# USBandPOWER.net
KiCad netlist of a schematic drawn in Altium Designer
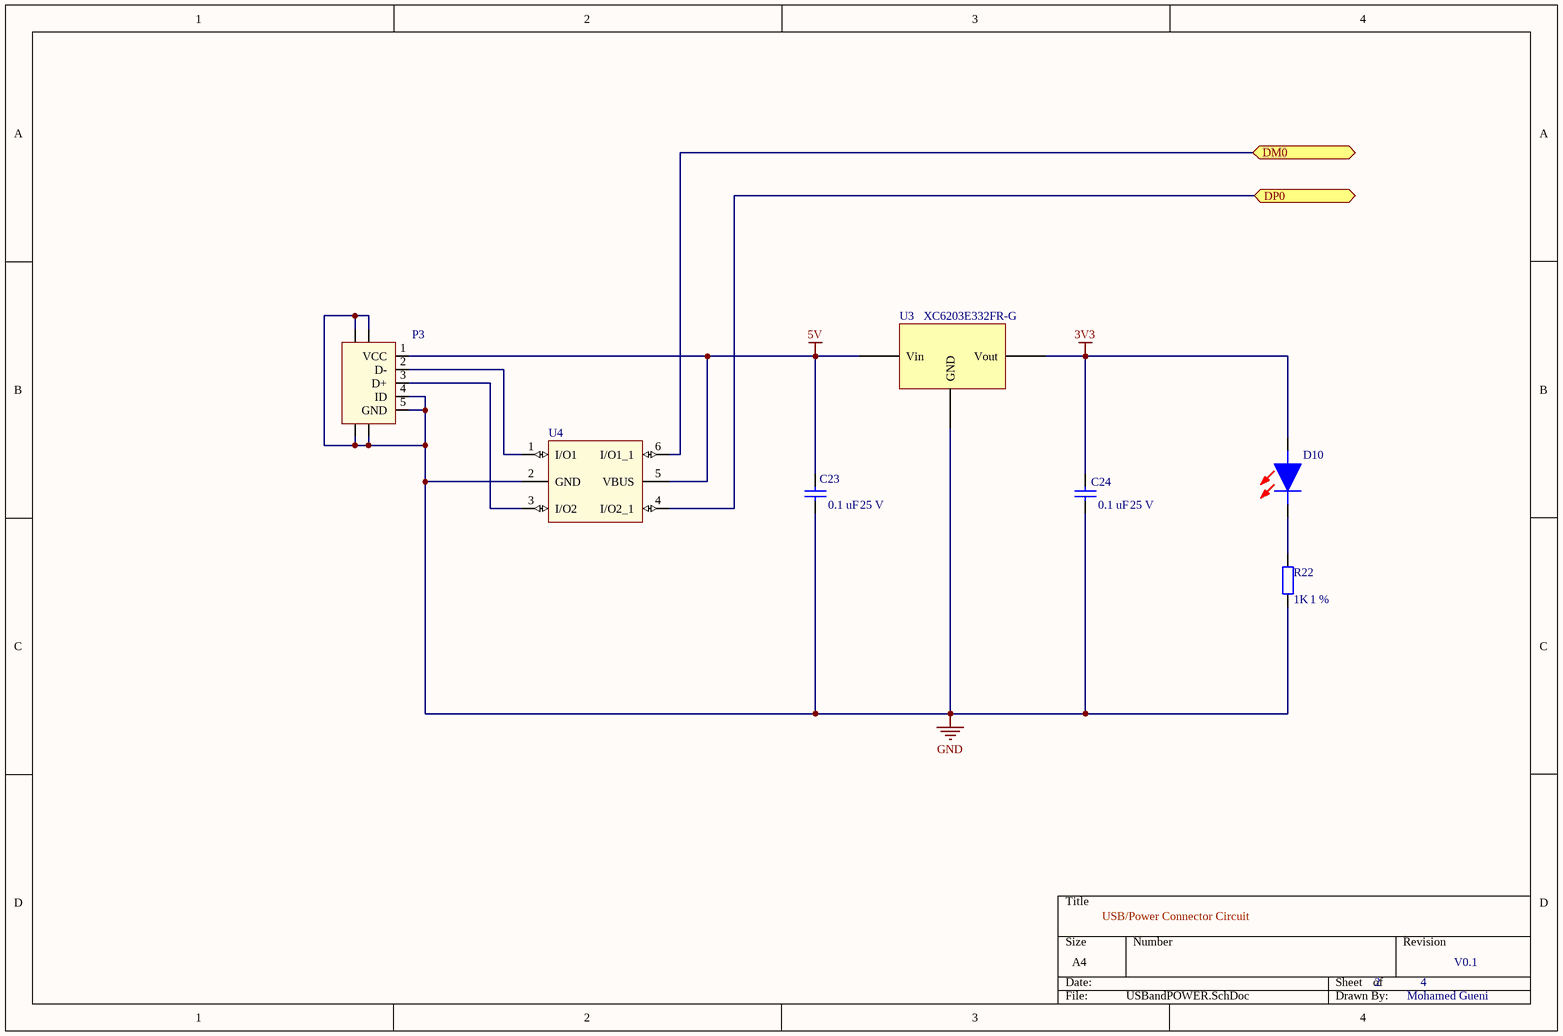
[diagram p0: USBandPOWER.SchDoc]

(export (version "E")
  (design (tool "Eeschema 10.0.6"))
  (components
    (comp (ref "C23")
      (value "Capacitor")
      (footprint "CAP0603")
      (fields (field (name "VALUE 1") "0.1 uF") (field (name "VALUE 2") "25 V"))
      (libsource (lib "Database_Libs1") (part "Capacitor"))
    )
    (comp (ref "C24")
      (value "Capacitor")
      (footprint "CAP0603")
      (fields (field (name "VALUE 1") "0.1 uF") (field (name "VALUE 2") "25 V"))
      (libsource (lib "Database_Libs1") (part "Capacitor"))
    )
    (comp (ref "D10")
      (value "SML-H12U8TT86C")
      (footprint "LEDC2012X90N")
      (description "ROHM - SML-H12U8TT86C - CHIP LED, AEC-Q101, RED, 40MCD, 0805")
      (fields (field (name "MOUSER PART NUMBER") "755-SML-H12U8TT86C"))
      (libsource (lib "Database_Libs1") (part "SML-H12U8TT86C"))
    )
    (comp (ref "P3")
      (value "USB_minB")
      (footprint "51387-0530")
      (libsource (lib "Database_Libs1") (part "USB_minB"))
    )
    (comp (ref "R22")
      (value "Resistor")
      (footprint "RES0603")
      (fields (field (name "VALUE 1") "1K") (field (name "TOL") "1 %"))
      (libsource (lib "Database_Libs1") (part "Resistor"))
    )
    (comp (ref "U3")
      (value "Voltage Regulator")
      (footprint "REG-SOT230P700X180-4N")
      (fields (field (name "MANREF") "XC6203E332FR-G"))
      (libsource (lib "Database_Libs1") (part "Voltage Regulator"))
    )
    (comp (ref "U4")
      (value "USBLC6-2SC6")
      (footprint "SOT95P280X145")
      (description "TVS Diode Array Uni-Directional USBLC6-2SC6 17V, SOT-23 6-Pin")
      (fields (field (name "MOUSER PART NUMBER") "511-USBLC6-2SC6"))
      (libsource (lib "Database_Libs1") (part "USBLC6-2SC6"))
    )
  )
  (nets
    (net (code "1") (name "/DM0") (class "Default")
      (node (ref "U4") (pin "6") (pinfunction "I/O1_1_6") (pintype "bidirectional"))
    )
    (net (code "2") (name "/DP0") (class "Default")
      (node (ref "U4") (pin "4") (pinfunction "I/O2_1_4") (pintype "bidirectional"))
    )
    (net (code "3") (name "3V3") (class "Default")
      (node (ref "C24") (pin "2") (pinfunction "2_2") (pintype "passive"))
      (node (ref "D10") (pin "2") (pinfunction "A_2") (pintype "passive"))
      (node (ref "U3") (pin "3") (pinfunction "Vout_3") (pintype "passive"))
    )
    (net (code "4") (name "5V") (class "Default")
      (node (ref "C23") (pin "2") (pinfunction "2_2") (pintype "passive"))
      (node (ref "P3") (pin "1") (pinfunction "VCC_1") (pintype "power_in"))
      (node (ref "U3") (pin "2") (pinfunction "Vin_2") (pintype "passive"))
      (node (ref "U4") (pin "5") (pinfunction "VBUS_5") (pintype "passive"))
    )
    (net (code "5") (name "GND") (class "Default")
      (node (ref "C23") (pin "1") (pinfunction "1_1") (pintype "passive"))
      (node (ref "C24") (pin "1") (pinfunction "1_1") (pintype "passive"))
      (node (ref "P3") (pin "4") (pinfunction "ID_4") (pintype "power_in"))
      (node (ref "P3") (pin "5") (pinfunction "GND_5") (pintype "power_in"))
      (node (ref "P3") (pin "SH1") (pinfunction "SHIELD_SH1") (pintype "power_in"))
      (node (ref "P3") (pin "SH2") (pinfunction "SHIELD_SH2") (pintype "power_in"))
      (node (ref "P3") (pin "SH3") (pinfunction "SHIELD_SH3") (pintype "power_in"))
      (node (ref "P3") (pin "SH4") (pinfunction "SHIELD_SH4") (pintype "power_in"))
      (node (ref "R22") (pin "1") (pinfunction "1_1") (pintype "passive"))
      (node (ref "U3") (pin "1") (pinfunction "GND_1") (pintype "passive"))
      (node (ref "U4") (pin "2") (pinfunction "GND_2") (pintype "passive"))
    )
    (net (code "6") (name "Net-(D10-K)") (class "Default")
      (node (ref "D10") (pin "1") (pinfunction "K_1") (pintype "passive"))
      (node (ref "R22") (pin "2") (pinfunction "2_2") (pintype "passive"))
    )
    (net (code "7") (name "Net-(P3-D+)") (class "Default")
      (node (ref "P3") (pin "3") (pinfunction "D+_3") (pintype "bidirectional"))
      (node (ref "U4") (pin "3") (pinfunction "I/O2_3") (pintype "bidirectional"))
    )
    (net (code "8") (name "Net-(P3-D-)") (class "Default")
      (node (ref "P3") (pin "2") (pinfunction "D-_2") (pintype "bidirectional"))
      (node (ref "U4") (pin "1") (pinfunction "I/O1_1") (pintype "bidirectional"))
    )
  )
)
